# SmallyMouse2.net
KiCad netlist of a schematic drawn in Altium Designer
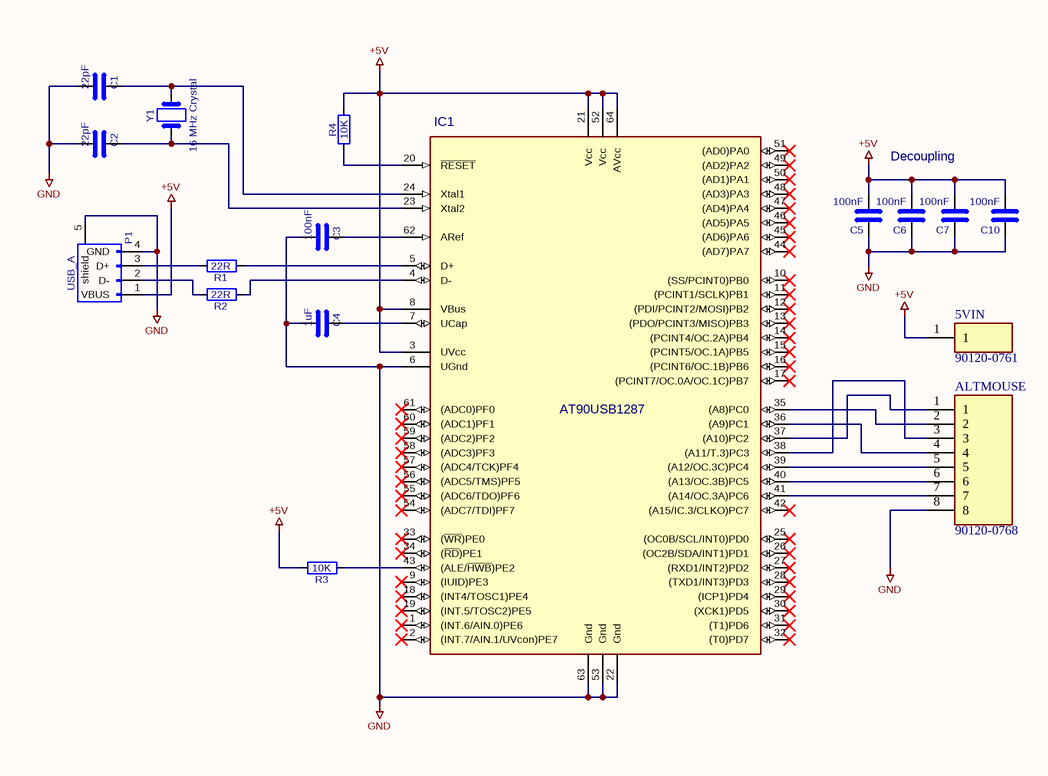
[diagram p0: SmallyMouse2.SchDoc]

(export (version "E")
  (design (tool "Eeschema 10.0.6"))
  (components
    (comp (ref "5VIN")
      (value "90120-0761")
      (footprint "SamacSys:HDRV1W90P0X254_1X1_232X249X560P")
      (description "Connector")
      (fields (field (name "MOUSER PART NUMBER") "538-90120-0761"))
      (libsource (lib "*") (part "90120-0761"))
    )
    (comp (ref "ALTMOUSE")
      (value "90120-0768")
      (footprint "SamacSys:HDRV8W90P0X254_1X8_2032X249X560P")
      (description "Connector")
      (fields (field (name "MOUSER PART NUMBER") "538-90120-0768"))
      (libsource (lib "*") (part "90120-0768"))
    )
    (comp (ref "C1") (value "22pF") (libsource (lib "*") (part "C")))
    (comp (ref "C2") (value "22pF") (libsource (lib "*") (part "C")))
    (comp (ref "C3") (value "100nF") (libsource (lib "*") (part "C")))
    (comp (ref "C4") (value "1uF") (libsource (lib "*") (part "C")))
    (comp (ref "C5") (value "100nF") (libsource (lib "*") (part "C")))
    (comp (ref "C6") (value "100nF") (libsource (lib "*") (part "C")))
    (comp (ref "C7") (value "100nF") (libsource (lib "*") (part "C")))
    (comp (ref "C10") (value "100nF") (libsource (lib "*") (part "C")))
    (comp (ref "IC1") (value "AT90USB1287") (libsource (lib "*") (part "AT90USB1287-RESCUE-SmallyMouse2")))
    (comp (ref "P1") (value "USB_A") (libsource (lib "*") (part "USB_A-RESCUE-SmallyMouse2")))
    (comp (ref "R1") (value "22R") (libsource (lib "*") (part "R")))
    (comp (ref "R2") (value "22R") (libsource (lib "*") (part "R")))
    (comp (ref "R3") (value "10K") (libsource (lib "*") (part "R")))
    (comp (ref "R4") (value "10K") (libsource (lib "") (part "R_1")))
    (comp (ref "Y1") (value "16 MHz Crystal") (libsource (lib "*") (part "Crystal")))
  )
  (nets
    (net (code "1") (name "+5V") (class "Default")
      (node (ref "5VIN") (pin "1") (pinfunction "1_1") (pintype "passive"))
      (node (ref "C10") (pin "2") (pinfunction "2_2") (pintype "passive"))
      (node (ref "C5") (pin "2") (pinfunction "2_2") (pintype "passive"))
      (node (ref "C6") (pin "2") (pinfunction "2_2") (pintype "passive"))
      (node (ref "C7") (pin "2") (pinfunction "2_2") (pintype "passive"))
      (node (ref "IC1") (pin "21") (pinfunction "Vcc_21") (pintype "power_in"))
      (node (ref "IC1") (pin "3") (pinfunction "UVcc_3") (pintype "power_in"))
      (node (ref "IC1") (pin "52") (pinfunction "Vcc_52") (pintype "power_in"))
      (node (ref "IC1") (pin "64") (pinfunction "AVcc_64") (pintype "power_in"))
      (node (ref "IC1") (pin "8") (pinfunction "VBus_8") (pintype "power_in"))
      (node (ref "P1") (pin "1") (pinfunction "VBUS_1") (pintype "power_in"))
      (node (ref "R3") (pin "2") (pinfunction "2_2") (pintype "passive"))
      (node (ref "R4") (pin "2") (pinfunction "2_2") (pintype "passive"))
    )
    (net (code "2") (name "GND") (class "Default")
      (node (ref "ALTMOUSE") (pin "8") (pinfunction "8_8") (pintype "passive"))
      (node (ref "C1") (pin "2") (pinfunction "2_2") (pintype "passive"))
      (node (ref "C10") (pin "1") (pinfunction "1_1") (pintype "passive"))
      (node (ref "C2") (pin "2") (pinfunction "2_2") (pintype "passive"))
      (node (ref "C3") (pin "2") (pinfunction "2_2") (pintype "passive"))
      (node (ref "C4") (pin "2") (pinfunction "2_2") (pintype "passive"))
      (node (ref "C5") (pin "1") (pinfunction "1_1") (pintype "passive"))
      (node (ref "C6") (pin "1") (pinfunction "1_1") (pintype "passive"))
      (node (ref "C7") (pin "1") (pinfunction "1_1") (pintype "passive"))
      (node (ref "IC1") (pin "22") (pinfunction "Gnd_22") (pintype "power_in"))
      (node (ref "IC1") (pin "53") (pinfunction "Gnd_53") (pintype "power_in"))
      (node (ref "IC1") (pin "6") (pinfunction "UGnd_6") (pintype "power_in"))
      (node (ref "IC1") (pin "63") (pinfunction "Gnd_63") (pintype "power_in"))
      (node (ref "P1") (pin "4") (pinfunction "GND_4") (pintype "power_in"))
      (node (ref "P1") (pin "5") (pinfunction "shield_5") (pintype "passive"))
    )
    (net (code "3") (name "Net-(IC1-(A8)PC0)") (class "Default")
      (node (ref "ALTMOUSE") (pin "2") (pinfunction "2_2") (pintype "passive"))
      (node (ref "IC1") (pin "35") (pinfunction "(A8)PC0_35") (pintype "bidirectional"))
    )
    (net (code "4") (name "Net-(IC1-(A9)PC1)") (class "Default")
      (node (ref "ALTMOUSE") (pin "4") (pinfunction "4_4") (pintype "passive"))
      (node (ref "IC1") (pin "36") (pinfunction "(A9)PC1_36") (pintype "bidirectional"))
    )
    (net (code "5") (name "Net-(IC1-(A10)PC2)") (class "Default")
      (node (ref "ALTMOUSE") (pin "1") (pinfunction "1_1") (pintype "passive"))
      (node (ref "IC1") (pin "37") (pinfunction "(A10)PC2_37") (pintype "bidirectional"))
    )
    (net (code "6") (name "Net-(IC1-(A11{slash}T.3)PC3)") (class "Default")
      (node (ref "ALTMOUSE") (pin "3") (pinfunction "3_3") (pintype "passive"))
      (node (ref "IC1") (pin "38") (pinfunction "(A11/T.3)PC3_38") (pintype "bidirectional"))
    )
    (net (code "7") (name "Net-(IC1-(A12{slash}OC.3C)PC4)") (class "Default")
      (node (ref "ALTMOUSE") (pin "5") (pinfunction "5_5") (pintype "passive"))
      (node (ref "IC1") (pin "39") (pinfunction "(A12/OC.3C)PC4_39") (pintype "bidirectional"))
    )
    (net (code "8") (name "Net-(IC1-(A13{slash}OC.3B)PC5)") (class "Default")
      (node (ref "ALTMOUSE") (pin "6") (pinfunction "6_6") (pintype "passive"))
      (node (ref "IC1") (pin "40") (pinfunction "(A13/OC.3B)PC5_40") (pintype "bidirectional"))
    )
    (net (code "9") (name "Net-(IC1-(A14{slash}OC.3A)PC6)") (class "Default")
      (node (ref "ALTMOUSE") (pin "7") (pinfunction "7_7") (pintype "passive"))
      (node (ref "IC1") (pin "41") (pinfunction "(A14/OC.3A)PC6_41") (pintype "bidirectional"))
    )
    (net (code "10") (name "Net-(IC1-(ALE{slash}~{HWB})PE2)") (class "Default")
      (node (ref "IC1") (pin "43") (pinfunction "(ALE/~{HWB})PE2_43") (pintype "bidirectional"))
      (node (ref "R3") (pin "1") (pinfunction "1_1") (pintype "passive"))
    )
    (net (code "11") (name "Net-(IC1-ARef)") (class "Default")
      (node (ref "C3") (pin "1") (pinfunction "1_1") (pintype "passive"))
      (node (ref "IC1") (pin "62") (pinfunction "ARef_62") (pintype "input"))
    )
    (net (code "12") (name "Net-(IC1-D+)") (class "Default")
      (node (ref "IC1") (pin "5") (pinfunction "D+_5") (pintype "bidirectional"))
      (node (ref "R1") (pin "1") (pinfunction "1_1") (pintype "passive"))
    )
    (net (code "13") (name "Net-(IC1-D-)") (class "Default")
      (node (ref "IC1") (pin "4") (pinfunction "D-_4") (pintype "bidirectional"))
      (node (ref "R2") (pin "1") (pinfunction "1_1") (pintype "passive"))
    )
    (net (code "14") (name "Net-(IC1-UCap)") (class "Default")
      (node (ref "C4") (pin "1") (pinfunction "1_1") (pintype "passive"))
      (node (ref "IC1") (pin "7") (pinfunction "UCap_7") (pintype "bidirectional"))
    )
    (net (code "15") (name "Net-(IC1-Xtal1)") (class "Default")
      (node (ref "C1") (pin "1") (pinfunction "1_1") (pintype "passive"))
      (node (ref "IC1") (pin "24") (pinfunction "Xtal1_24") (pintype "input"))
      (node (ref "Y1") (pin "2") (pinfunction "2_2") (pintype "passive"))
    )
    (net (code "16") (name "Net-(IC1-Xtal2)") (class "Default")
      (node (ref "C2") (pin "1") (pinfunction "1_1") (pintype "passive"))
      (node (ref "IC1") (pin "23") (pinfunction "Xtal2_23") (pintype "input"))
      (node (ref "Y1") (pin "1") (pinfunction "1_1") (pintype "passive"))
    )
    (net (code "17") (name "Net-(IC1-~{RESET})") (class "Default")
      (node (ref "IC1") (pin "20") (pinfunction "~{RESET}_20") (pintype "input"))
      (node (ref "R4") (pin "1") (pinfunction "1_1") (pintype "passive"))
    )
    (net (code "18") (name "Net-(P1-D+)") (class "Default")
      (node (ref "P1") (pin "3") (pinfunction "D+_3") (pintype "passive"))
      (node (ref "R1") (pin "2") (pinfunction "2_2") (pintype "passive"))
    )
    (net (code "19") (name "Net-(P1-D-)") (class "Default")
      (node (ref "P1") (pin "2") (pinfunction "D-_2") (pintype "passive"))
      (node (ref "R2") (pin "2") (pinfunction "2_2") (pintype "passive"))
    )
    (net (code "20") (name "unconnected-(IC1-(A15{slash}IC.3{slash}CLKO)PC7-Pad42)") (class "Default")
      (node (ref "IC1") (pin "42") (pinfunction "(A15/IC.3/CLKO)PC7_42") (pintype "bidirectional+no_connect"))
    )
    (net (code "21") (name "unconnected-(IC1-(AD0)PA0-Pad51)") (class "Default")
      (node (ref "IC1") (pin "51") (pinfunction "(AD0)PA0_51") (pintype "bidirectional+no_connect"))
    )
    (net (code "22") (name "unconnected-(IC1-(AD1)PA1-Pad50)") (class "Default")
      (node (ref "IC1") (pin "50") (pinfunction "(AD1)PA1_50") (pintype "bidirectional+no_connect"))
    )
    (net (code "23") (name "unconnected-(IC1-(AD2)PA2-Pad49)") (class "Default")
      (node (ref "IC1") (pin "49") (pinfunction "(AD2)PA2_49") (pintype "bidirectional+no_connect"))
    )
    (net (code "24") (name "unconnected-(IC1-(AD3)PA3-Pad48)") (class "Default")
      (node (ref "IC1") (pin "48") (pinfunction "(AD3)PA3_48") (pintype "bidirectional+no_connect"))
    )
    (net (code "25") (name "unconnected-(IC1-(AD4)PA4-Pad47)") (class "Default")
      (node (ref "IC1") (pin "47") (pinfunction "(AD4)PA4_47") (pintype "bidirectional+no_connect"))
    )
    (net (code "26") (name "unconnected-(IC1-(AD5)PA5-Pad46)") (class "Default")
      (node (ref "IC1") (pin "46") (pinfunction "(AD5)PA5_46") (pintype "bidirectional+no_connect"))
    )
    (net (code "27") (name "unconnected-(IC1-(AD6)PA6-Pad45)") (class "Default")
      (node (ref "IC1") (pin "45") (pinfunction "(AD6)PA6_45") (pintype "bidirectional+no_connect"))
    )
    (net (code "28") (name "unconnected-(IC1-(AD7)PA7-Pad44)") (class "Default")
      (node (ref "IC1") (pin "44") (pinfunction "(AD7)PA7_44") (pintype "bidirectional+no_connect"))
    )
    (net (code "29") (name "unconnected-(IC1-(ADC0)PF0-Pad61)") (class "Default")
      (node (ref "IC1") (pin "61") (pinfunction "(ADC0)PF0_61") (pintype "bidirectional+no_connect"))
    )
    (net (code "30") (name "unconnected-(IC1-(ADC1)PF1-Pad60)") (class "Default")
      (node (ref "IC1") (pin "60") (pinfunction "(ADC1)PF1_60") (pintype "bidirectional+no_connect"))
    )
    (net (code "31") (name "unconnected-(IC1-(ADC2)PF2-Pad59)") (class "Default")
      (node (ref "IC1") (pin "59") (pinfunction "(ADC2)PF2_59") (pintype "bidirectional+no_connect"))
    )
    (net (code "32") (name "unconnected-(IC1-(ADC3)PF3-Pad58)") (class "Default")
      (node (ref "IC1") (pin "58") (pinfunction "(ADC3)PF3_58") (pintype "bidirectional+no_connect"))
    )
    (net (code "33") (name "unconnected-(IC1-(ADC4{slash}TCK)PF4-Pad57)") (class "Default")
      (node (ref "IC1") (pin "57") (pinfunction "(ADC4/TCK)PF4_57") (pintype "bidirectional+no_connect"))
    )
    (net (code "34") (name "unconnected-(IC1-(ADC5{slash}TMS)PF5-Pad56)") (class "Default")
      (node (ref "IC1") (pin "56") (pinfunction "(ADC5/TMS)PF5_56") (pintype "bidirectional+no_connect"))
    )
    (net (code "35") (name "unconnected-(IC1-(ADC6{slash}TDO)PF6-Pad55)") (class "Default")
      (node (ref "IC1") (pin "55") (pinfunction "(ADC6/TDO)PF6_55") (pintype "bidirectional+no_connect"))
    )
    (net (code "36") (name "unconnected-(IC1-(ADC7{slash}TDI)PF7-Pad54)") (class "Default")
      (node (ref "IC1") (pin "54") (pinfunction "(ADC7/TDI)PF7_54") (pintype "bidirectional+no_connect"))
    )
    (net (code "37") (name "unconnected-(IC1-(ICP1)PD4-Pad29)") (class "Default")
      (node (ref "IC1") (pin "29") (pinfunction "(ICP1)PD4_29") (pintype "bidirectional+no_connect"))
    )
    (net (code "38") (name "unconnected-(IC1-(INT.5{slash}TOSC2)PE5-Pad19)") (class "Default")
      (node (ref "IC1") (pin "19") (pinfunction "(INT.5/TOSC2)PE5_19") (pintype "bidirectional+no_connect"))
    )
    (net (code "39") (name "unconnected-(IC1-(INT.6{slash}AIN.0)PE6-Pad1)") (class "Default")
      (node (ref "IC1") (pin "1") (pinfunction "(INT.6/AIN.0)PE6_1") (pintype "bidirectional+no_connect"))
    )
    (net (code "40") (name "unconnected-(IC1-(INT.7{slash}AIN.1{slash}UVcon)PE7-Pad2)") (class "Default")
      (node (ref "IC1") (pin "2") (pinfunction "(INT.7/AIN.1/UVcon)PE7_2") (pintype "bidirectional+no_connect"))
    )
    (net (code "41") (name "unconnected-(IC1-(INT4{slash}TOSC1)PE4-Pad18)") (class "Default")
      (node (ref "IC1") (pin "18") (pinfunction "(INT4/TOSC1)PE4_18") (pintype "bidirectional+no_connect"))
    )
    (net (code "42") (name "unconnected-(IC1-(IUID)PE3-Pad9)") (class "Default")
      (node (ref "IC1") (pin "9") (pinfunction "(IUID)PE3_9") (pintype "bidirectional+no_connect"))
    )
    (net (code "43") (name "unconnected-(IC1-(OC0B{slash}SCL{slash}INT0)PD0-Pad25)") (class "Default")
      (node (ref "IC1") (pin "25") (pinfunction "(OC0B/SCL/INT0)PD0_25") (pintype "bidirectional+no_connect"))
    )
    (net (code "44") (name "unconnected-(IC1-(OC2B{slash}SDA{slash}INT1)PD1-Pad26)") (class "Default")
      (node (ref "IC1") (pin "26") (pinfunction "(OC2B/SDA/INT1)PD1_26") (pintype "bidirectional+no_connect"))
    )
    (net (code "45") (name "unconnected-(IC1-(PCINT1{slash}SCLK)PB1-Pad11)") (class "Default")
      (node (ref "IC1") (pin "11") (pinfunction "(PCINT1/SCLK)PB1_11") (pintype "bidirectional+no_connect"))
    )
    (net (code "46") (name "unconnected-(IC1-(PCINT4{slash}OC.2A)PB4-Pad14)") (class "Default")
      (node (ref "IC1") (pin "14") (pinfunction "(PCINT4/OC.2A)PB4_14") (pintype "bidirectional+no_connect"))
    )
    (net (code "47") (name "unconnected-(IC1-(PCINT5{slash}OC.1A)PB5-Pad15)") (class "Default")
      (node (ref "IC1") (pin "15") (pinfunction "(PCINT5/OC.1A)PB5_15") (pintype "bidirectional+no_connect"))
    )
    (net (code "48") (name "unconnected-(IC1-(PCINT6{slash}OC.1B)PB6-Pad16)") (class "Default")
      (node (ref "IC1") (pin "16") (pinfunction "(PCINT6/OC.1B)PB6_16") (pintype "bidirectional+no_connect"))
    )
    (net (code "49") (name "unconnected-(IC1-(PCINT7{slash}OC.0A{slash}OC.1C)PB7-Pad17)") (class "Default")
      (node (ref "IC1") (pin "17") (pinfunction "(PCINT7/OC.0A/OC.1C)PB7_17") (pintype "bidirectional+no_connect"))
    )
    (net (code "50") (name "unconnected-(IC1-(PDI{slash}PCINT2{slash}MOSI)PB2-Pad12)") (class "Default")
      (node (ref "IC1") (pin "12") (pinfunction "(PDI/PCINT2/MOSI)PB2_12") (pintype "bidirectional+no_connect"))
    )
    (net (code "51") (name "unconnected-(IC1-(PDO{slash}PCINT3{slash}MISO)PB3-Pad13)") (class "Default")
      (node (ref "IC1") (pin "13") (pinfunction "(PDO/PCINT3/MISO)PB3_13") (pintype "bidirectional+no_connect"))
    )
    (net (code "52") (name "unconnected-(IC1-(RXD1{slash}INT2)PD2-Pad27)") (class "Default")
      (node (ref "IC1") (pin "27") (pinfunction "(RXD1/INT2)PD2_27") (pintype "bidirectional+no_connect"))
    )
    (net (code "53") (name "unconnected-(IC1-(SS{slash}PCINT0)PB0-Pad10)") (class "Default")
      (node (ref "IC1") (pin "10") (pinfunction "(SS/PCINT0)PB0_10") (pintype "bidirectional+no_connect"))
    )
    (net (code "54") (name "unconnected-(IC1-(T0)PD7-Pad32)") (class "Default")
      (node (ref "IC1") (pin "32") (pinfunction "(T0)PD7_32") (pintype "bidirectional+no_connect"))
    )
    (net (code "55") (name "unconnected-(IC1-(T1)PD6-Pad31)") (class "Default")
      (node (ref "IC1") (pin "31") (pinfunction "(T1)PD6_31") (pintype "bidirectional+no_connect"))
    )
    (net (code "56") (name "unconnected-(IC1-(TXD1{slash}INT3)PD3-Pad28)") (class "Default")
      (node (ref "IC1") (pin "28") (pinfunction "(TXD1/INT3)PD3_28") (pintype "bidirectional+no_connect"))
    )
    (net (code "57") (name "unconnected-(IC1-(XCK1)PD5-Pad30)") (class "Default")
      (node (ref "IC1") (pin "30") (pinfunction "(XCK1)PD5_30") (pintype "bidirectional+no_connect"))
    )
    (net (code "58") (name "unconnected-(IC1-(~{RD})PE1-Pad34)") (class "Default")
      (node (ref "IC1") (pin "34") (pinfunction "(~{RD})PE1_34") (pintype "bidirectional+no_connect"))
    )
    (net (code "59") (name "unconnected-(IC1-(~{WR})PE0-Pad33)") (class "Default")
      (node (ref "IC1") (pin "33") (pinfunction "(~{WR})PE0_33") (pintype "bidirectional+no_connect"))
    )
  )
)
